# ADC_40M20b.net
KiCad netlist of a schematic drawn in Altium Designer
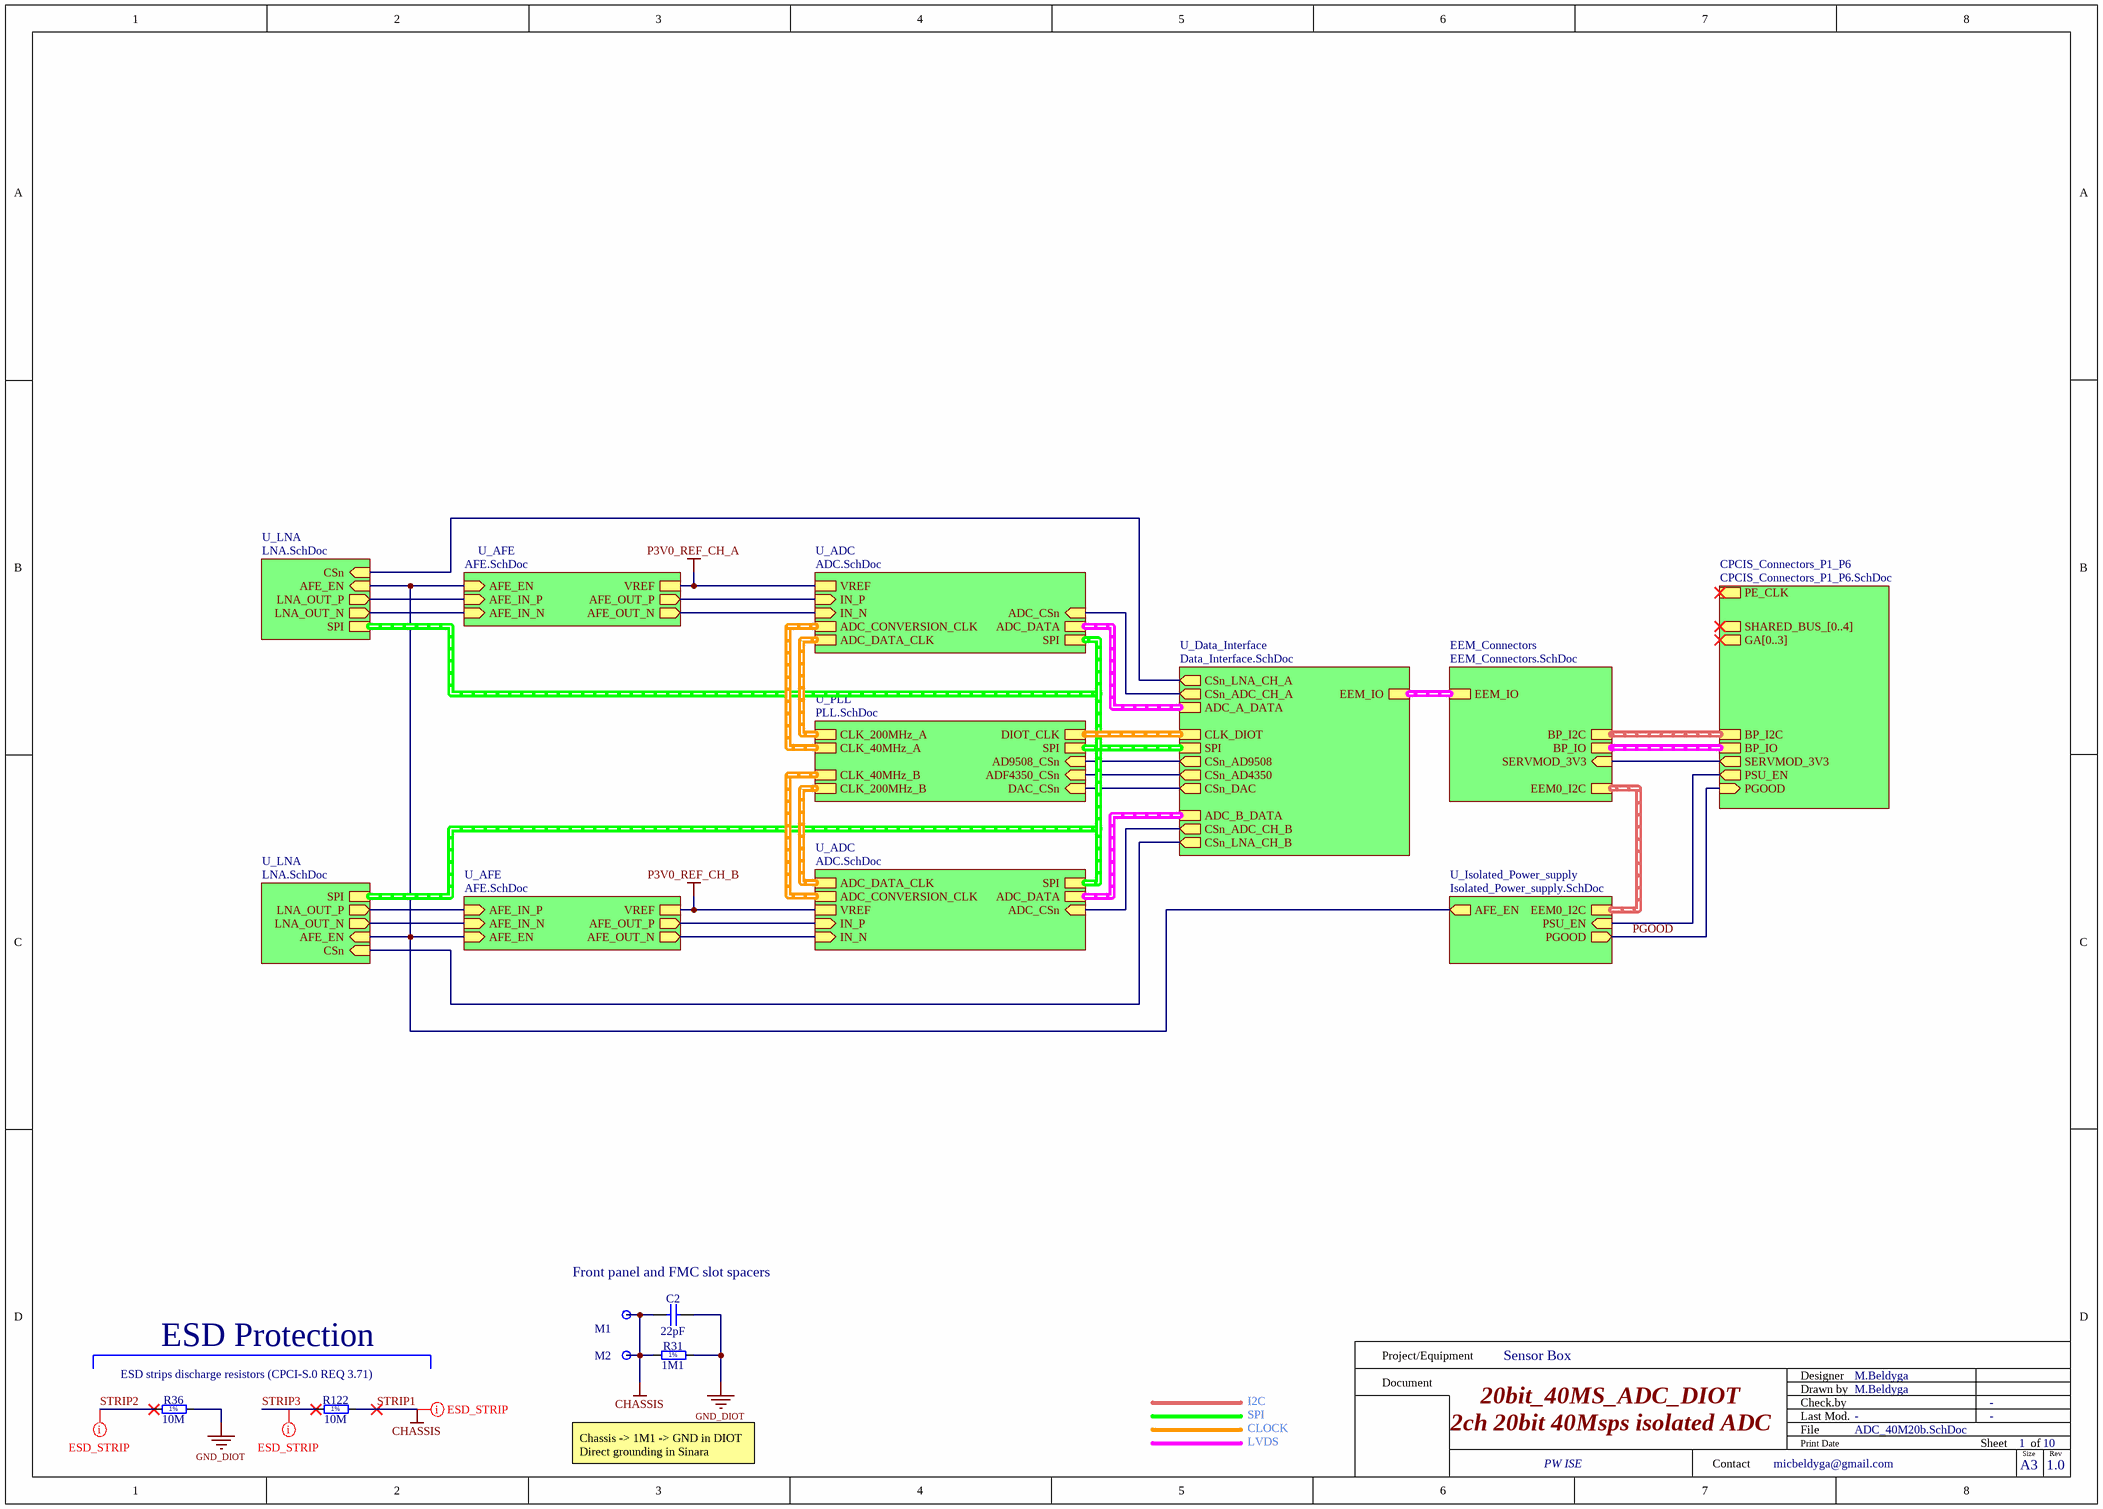
[diagram p0: ADC_40M20b.SchDoc]

(export (version "E")
  (design (tool "Eeschema 10.0.6"))
  (components
    (comp (ref "C2")
      (value "22pF")
      (footprint "CAPC1005X55N")
      (description "Non-polarised capacitor")
      (fields
        (field (name "PART NUMBER") "CC0402_22PF_50V_5%_C0G")
        (field (name "VOLTAGE") "50V")
        (field (name "AUTHOR") "CERN DEM JLC")
      )
      (libsource (lib "Capacitors") (part "Capacitor - non polarized"))
    )
    (comp (ref "M1")
      (value "Plated Hole")
      (footprint "MTG300_600")
      (description "Single Terminal Socket")
      (fields (field (name "PART NUMBER") "PLATED_HOLE3.0_PAD6.0") (field (name "AUTHOR") "CERN DEM JLC"))
      (libsource (lib "Eletro-mechanical") (part "Single Terminal Socket"))
    )
    (comp (ref "M2")
      (value "Plated Hole")
      (footprint "MTG300_600")
      (description "Single Terminal Socket")
      (fields (field (name "PART NUMBER") "PLATED_HOLE3.0_PAD6.0") (field (name "AUTHOR") "CERN DEM JLC"))
      (libsource (lib "Eletro-mechanical") (part "Single Terminal Socket"))
    )
    (comp (ref "R31")
      (value "1M1")
      (footprint "RESC2012X60N")
      (description "Resistor - 1%")
      (fields
        (field (name "PART NUMBER") "R0805_1M1_1%_0.125W_100PPM")
        (field (name "MANUFACTURER") "GENERIC")
        (field (name "AUTHOR") "CERN DEM JLC")
      )
      (libsource (lib "Resistors") (part "Resistor - 1%"))
    )
    (comp (ref "R36")
      (value "10M")
      (footprint "RESC2113X55N")
      (description "Resistor - 1%")
      (fields
        (field (name "PART NUMBER") "R0805_10M_1%_0.125W_100PPM_VISHAY_CRCW e3")
        (field (name "POWER") "0.125W")
        (field (name "AUTHOR") "CERN DEM BC")
      )
      (libsource (lib "Resistors") (part "Resistor - 1%"))
    )
    (comp (ref "R122")
      (value "10M")
      (footprint "RESC2113X55N")
      (description "Resistor - 1%")
      (fields
        (field (name "PART NUMBER") "R0805_10M_1%_0.125W_100PPM_VISHAY_CRCW e3")
        (field (name "POWER") "0.125W")
        (field (name "AUTHOR") "CERN DEM BC")
      )
      (libsource (lib "Resistors") (part "Resistor - 1%"))
    )
  )
  (nets
    (net (code "36") (name "/STRIP2") (class "Default")
      (node (ref "R36") (pin "1") (pinfunction "1_1") (pintype "passive+no_connect"))
    )
    (net (code "37") (name "/STRIP3") (class "Default")
      (node (ref "R122") (pin "1") (pinfunction "1_1") (pintype "passive+no_connect"))
    )
    (net (code "38") (name "CHASSIS") (class "Default")
      (node (ref "C2") (pin "1") (pinfunction "1_1") (pintype "passive"))
      (node (ref "M1") (pin "1") (pinfunction "1_1") (pintype "bidirectional"))
      (node (ref "M2") (pin "1") (pinfunction "1_1") (pintype "bidirectional"))
      (node (ref "R122") (pin "2") (pinfunction "2_2") (pintype "passive"))
      (node (ref "R31") (pin "1") (pinfunction "1_1") (pintype "passive"))
    )
    (net (code "39") (name "GND_DIOT") (class "Default")
      (node (ref "C2") (pin "2") (pinfunction "2_2") (pintype "passive"))
      (node (ref "R31") (pin "2") (pinfunction "2_2") (pintype "passive"))
      (node (ref "R36") (pin "2") (pinfunction "2_2") (pintype "passive"))
    )
  )
)
